# board1.net
KiCad netlist of a schematic drawn in Altium Designer
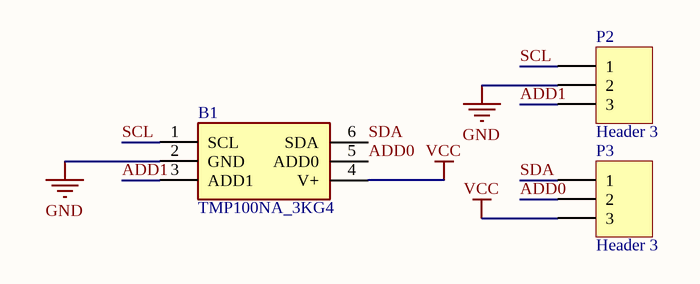
[diagram p0: board1.SchDoc]

(export (version "E")
  (design (tool "Eeschema 10.0.6"))
  (components
    (comp (ref "B1")
      (value "TMP100NA_3KG4")
      (footprint "SOT95P280X145-6N")
      (description "Board Mount Temperature Sensors Digital Temp Sensor w/I2C Ser Interface")
      (fields
        (field (name "MOUSER PART NUMBER") "595-TMP100NA/3KG4")
        (field (name "MANUFACTURER_PART_NUMBER") "TMP100NA/3KG4")
      )
      (libsource (lib "TMP100NA_3KG4") (part "TMP100NA_3KG4"))
    )
    (comp (ref "P2")
      (value "Header 3")
      (footprint "HDR1X3")
      (description "Header, 3-Pin")
      (fields (field (name "PUBLISHER") "Altium Limited"))
      (libsource (lib "Miscellaneous Connectors") (part "Header 3"))
    )
    (comp (ref "P3")
      (value "Header 3")
      (footprint "HDR1X3")
      (description "Header, 3-Pin")
      (fields (field (name "PUBLISHER") "Altium Limited"))
      (libsource (lib "Miscellaneous Connectors") (part "Header 3"))
    )
  )
  (nets
    (net (code "1") (name "/ADD0") (class "Default")
      (node (ref "B1") (pin "5") (pinfunction "ADD0_5") (pintype "passive"))
      (node (ref "P3") (pin "2") (pinfunction "2_2") (pintype "passive"))
    )
    (net (code "2") (name "/ADD1") (class "Default")
      (node (ref "B1") (pin "3") (pinfunction "ADD1_3") (pintype "passive"))
      (node (ref "P2") (pin "3") (pinfunction "3_3") (pintype "passive"))
    )
    (net (code "3") (name "/SCL") (class "Default")
      (node (ref "B1") (pin "1") (pinfunction "SCL_1") (pintype "passive"))
      (node (ref "P2") (pin "1") (pinfunction "1_1") (pintype "passive"))
    )
    (net (code "4") (name "/SDA") (class "Default")
      (node (ref "B1") (pin "6") (pinfunction "SDA_6") (pintype "passive"))
      (node (ref "P3") (pin "1") (pinfunction "1_1") (pintype "passive"))
    )
    (net (code "5") (name "GND") (class "Default")
      (node (ref "B1") (pin "2") (pinfunction "GND_2") (pintype "passive"))
      (node (ref "P2") (pin "2") (pinfunction "2_2") (pintype "passive"))
    )
    (net (code "6") (name "VCC") (class "Default")
      (node (ref "B1") (pin "4") (pinfunction "V+_4") (pintype "passive"))
      (node (ref "P3") (pin "3") (pinfunction "3_3") (pintype "passive"))
    )
  )
)
